# detectino-raspi.net
KiCad netlist of a schematic drawn in EAGLE
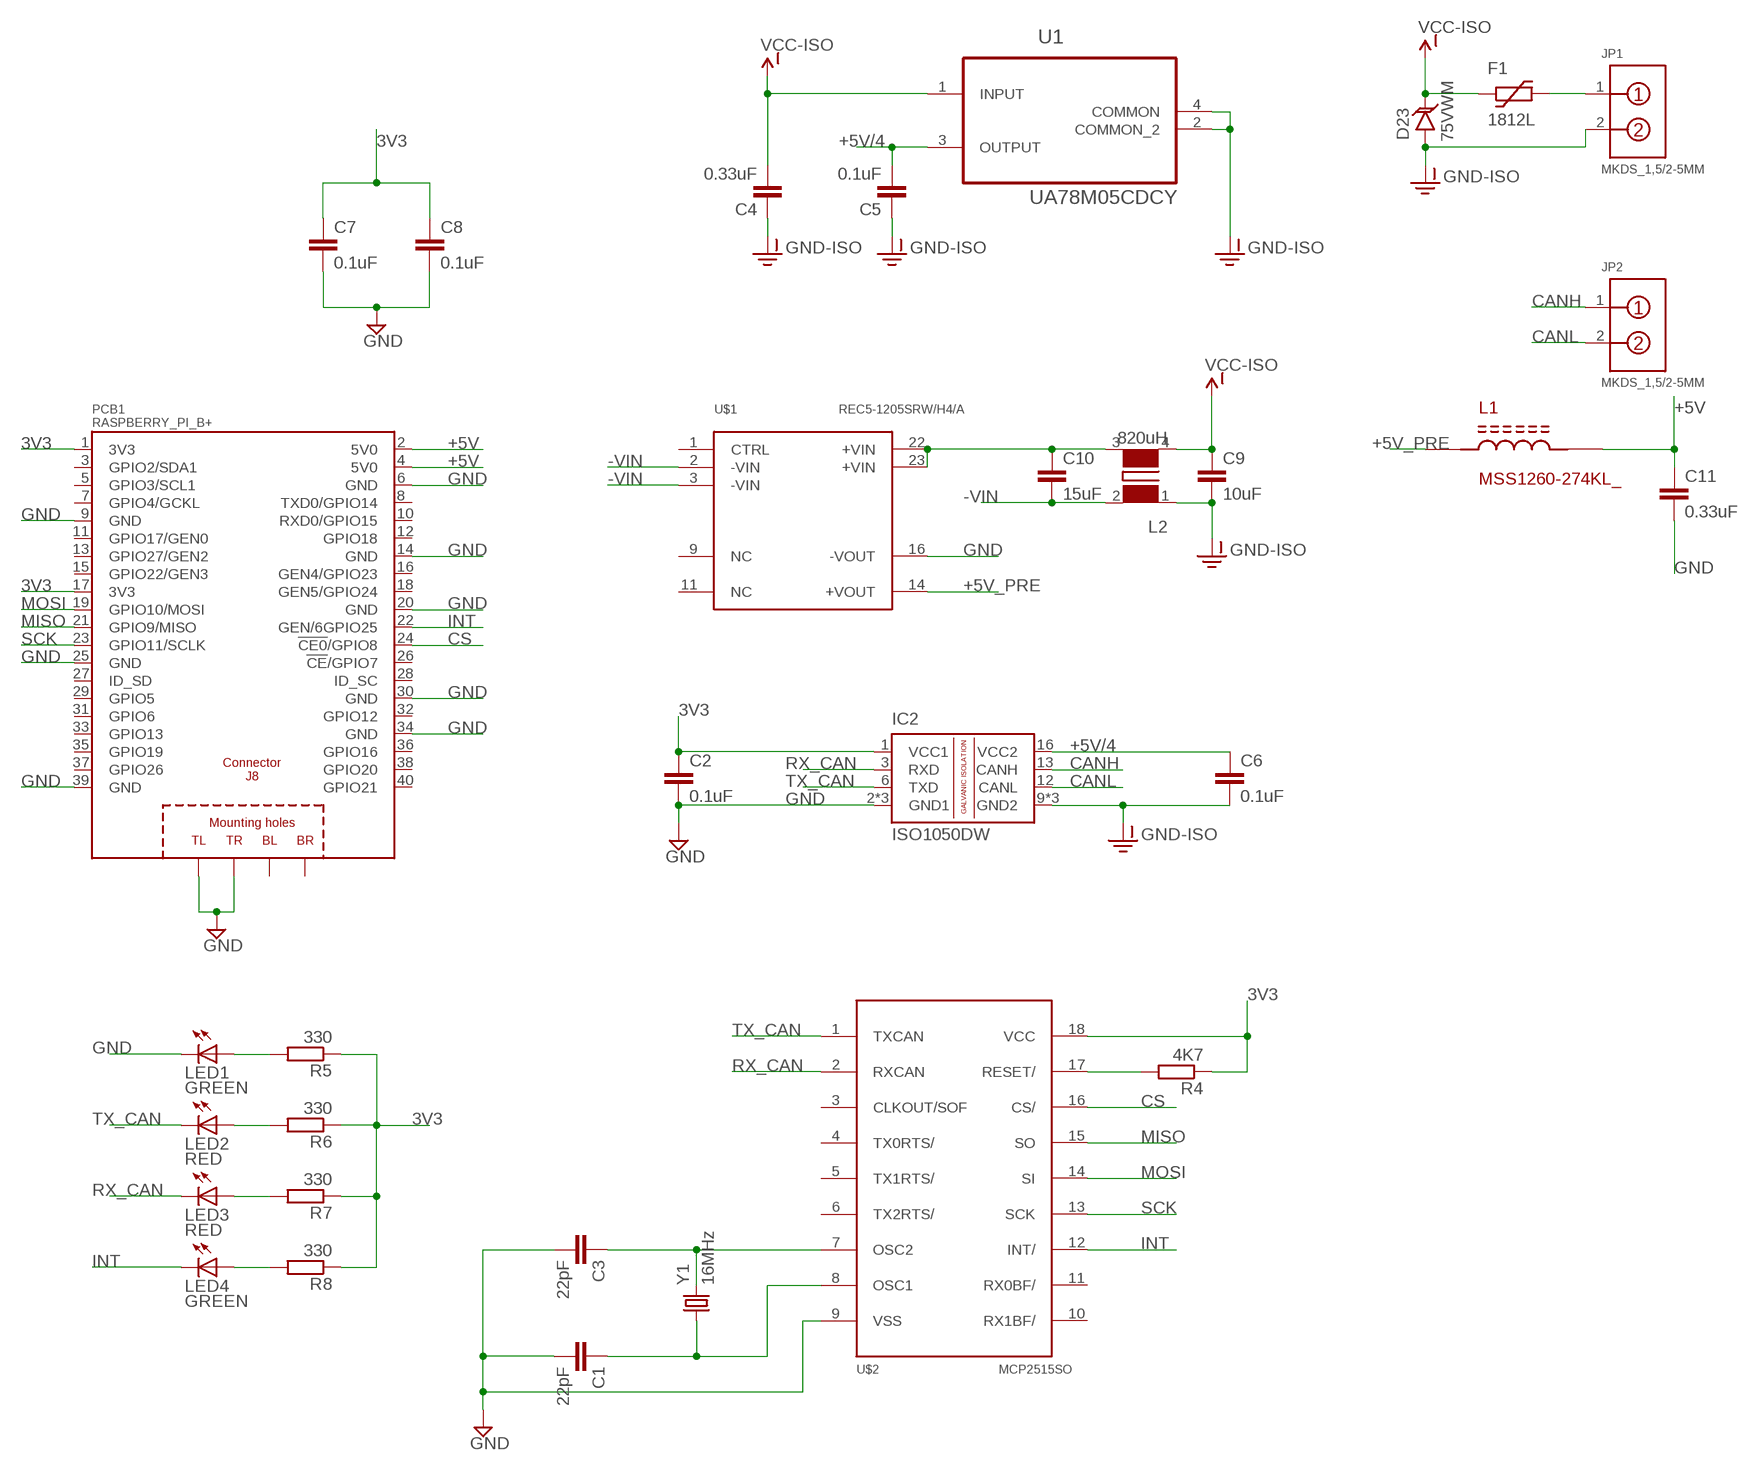
[diagram p0: schematic, sheet 1]

(export (version "E")
  (design (tool "Eeschema 10.0.6"))
  (components
    (comp (ref "C1")
      (value "22pF")
      (footprint "eagle-import:C1206K")
      (libsource (lib "eagle-import") (part "C-EUC1206K"))
    )
    (comp (ref "C2")
      (value "0.1uF")
      (footprint "eagle-import:C1206K")
      (libsource (lib "eagle-import") (part "C-EUC1206K"))
    )
    (comp (ref "C3")
      (value "22pF")
      (footprint "eagle-import:C1206K")
      (libsource (lib "eagle-import") (part "C-EUC1206K"))
    )
    (comp (ref "C4")
      (value "0.33uF")
      (footprint "eagle-import:C1206K")
      (libsource (lib "eagle-import") (part "C-EUC1206K"))
    )
    (comp (ref "C5")
      (value "0.1uF")
      (footprint "eagle-import:C1206K")
      (libsource (lib "eagle-import") (part "C-EUC1206K"))
    )
    (comp (ref "C6")
      (value "0.1uF")
      (footprint "eagle-import:C1206K")
      (libsource (lib "eagle-import") (part "C-EUC1206K"))
    )
    (comp (ref "C7")
      (value "0.1uF")
      (footprint "eagle-import:C1206K")
      (libsource (lib "eagle-import") (part "C-EUC1206K"))
    )
    (comp (ref "C8")
      (value "0.1uF")
      (footprint "eagle-import:C1206K")
      (libsource (lib "eagle-import") (part "C-EUC1206K"))
    )
    (comp (ref "C9")
      (value "10uF")
      (footprint "eagle-import:C1812K")
      (libsource (lib "eagle-import") (part "C-EUC1812K"))
    )
    (comp (ref "C10")
      (value "15uF")
      (footprint "eagle-import:C1812K")
      (libsource (lib "eagle-import") (part "C-EUC1812K"))
    )
    (comp (ref "C11")
      (value "0.33uF")
      (footprint "eagle-import:C1206K")
      (libsource (lib "eagle-import") (part "C-EUC1206K"))
    )
    (comp (ref "D23")
      (value "75VWM")
      (footprint "eagle-import:SMC")
      (libsource (lib "eagle-import") (part "TVS75VWM"))
    )
    (comp (ref "F1")
      (value "1812L")
      (footprint "eagle-import:1812L")
      (libsource (lib "eagle-import") (part "1812L"))
    )
    (comp (ref "IC2")
      (value "ISO1050DW")
      (footprint "eagle-import:SO-16DW")
      (libsource (lib "eagle-import") (part "ISO1050DW"))
    )
    (comp (ref "JP1")
      (value "MKDS_1,5/2-5MM")
      (footprint "eagle-import:MKDS_1,5_2-5MM")
      (libsource (lib "eagle-import") (part "MKDS_1,5/2-5MM"))
    )
    (comp (ref "JP2")
      (value "MKDS_1,5/2-5MM")
      (footprint "eagle-import:MKDS_1,5_2-5MM")
      (libsource (lib "eagle-import") (part "MKDS_1,5/2-5MM"))
    )
    (comp (ref "L1")
      (value "MSS1260-274KL_")
      (footprint "eagle-import:MSS1260")
      (libsource (lib "eagle-import") (part "MSS1260-274KL_"))
    )
    (comp (ref "L2")
      (value "820uH")
      (footprint "eagle-import:WE-FC_ET")
      (fields (field (name "MPN") "7448640395"))
      (libsource (lib "eagle-import") (part "WE-FC_ET-7448640395"))
    )
    (comp (ref "LED1")
      (value "GREEN")
      (footprint "eagle-import:SML1206")
      (libsource (lib "eagle-import") (part "LEDSML1206"))
    )
    (comp (ref "LED2")
      (value "RED")
      (footprint "eagle-import:SML1206")
      (libsource (lib "eagle-import") (part "LEDSML1206"))
    )
    (comp (ref "LED3")
      (value "RED")
      (footprint "eagle-import:SML1206")
      (libsource (lib "eagle-import") (part "LEDSML1206"))
    )
    (comp (ref "LED4")
      (value "GREEN")
      (footprint "eagle-import:SML1206")
      (libsource (lib "eagle-import") (part "LEDSML1206"))
    )
    (comp (ref "PCB1")
      (value "RASPBERRY_PI_B+")
      (footprint "eagle-import:RASPBERRY_PI_B+")
      (libsource (lib "eagle-import") (part "RASPBERRY_PI_B+"))
    )
    (comp (ref "R4")
      (value "4K7")
      (footprint "eagle-import:R1206")
      (libsource (lib "eagle-import") (part "R-EU_R1206"))
    )
    (comp (ref "R5")
      (value "330")
      (footprint "eagle-import:R1206")
      (libsource (lib "eagle-import") (part "R-EU_R1206"))
    )
    (comp (ref "R6")
      (value "330")
      (footprint "eagle-import:R1206")
      (libsource (lib "eagle-import") (part "R-EU_R1206"))
    )
    (comp (ref "R7")
      (value "330")
      (footprint "eagle-import:R1206")
      (libsource (lib "eagle-import") (part "R-EU_R1206"))
    )
    (comp (ref "R8")
      (value "330")
      (footprint "eagle-import:R1206")
      (libsource (lib "eagle-import") (part "R-EU_R1206"))
    )
    (comp (ref "U$1")
      (value "REC5-1205SRW/H4/A")
      (footprint "eagle-import:DIP24")
      (libsource (lib "eagle-import") (part "REC5-1205SRW/H4/A"))
    )
    (comp (ref "U$2")
      (value "MCP2515SO")
      (footprint "eagle-import:SO18L")
      (libsource (lib "eagle-import") (part "MCP2515SO"))
    )
    (comp (ref "U1")
      (value "UA78M05CDCY")
      (footprint "eagle-import:SOT230P700X180-4N")
      (libsource (lib "eagle-import") (part "UA78M05CDCY"))
    )
    (comp (ref "Y1")
      (value "16MHz")
      (footprint "eagle-import:HC49US")
      (libsource (lib "eagle-import") (part "CRYSTALHC49US"))
    )
  )
  (nets
    (net (code "1") (name "/+5V") (class "Default")
      (node (ref "C11") (pin "1") (pinfunction "1_1") (pintype "passive"))
      (node (ref "L1") (pin "P$2") (pinfunction "P$2_P$2") (pintype "bidirectional"))
      (node (ref "PCB1") (pin "2") (pinfunction "5V0_2") (pintype "power_in"))
      (node (ref "PCB1") (pin "4") (pinfunction "5V0_4") (pintype "power_in"))
    )
    (net (code "2") (name "/+5V_PRE") (class "Default")
      (node (ref "L1") (pin "P$1") (pinfunction "P$1_P$1") (pintype "bidirectional"))
      (node (ref "U$1") (pin "14") (pinfunction "+VOUT_14") (pintype "power_in"))
    )
    (net (code "3") (name "/+5V{slash}4") (class "Default")
      (node (ref "C5") (pin "2") (pinfunction "2_2") (pintype "passive"))
      (node (ref "C6") (pin "1") (pinfunction "1_1") (pintype "passive"))
      (node (ref "IC2") (pin "16") (pinfunction "VCC2_16") (pintype "input"))
      (node (ref "U1") (pin "3") (pinfunction "OUTPUT_3") (pintype "input"))
    )
    (net (code "4") (name "/-VIN") (class "Default")
      (node (ref "C10") (pin "2") (pinfunction "2_2") (pintype "passive"))
      (node (ref "L2") (pin "2") (pinfunction "4_2") (pintype "passive"))
      (node (ref "U$1") (pin "2") (pinfunction "-VIN_2") (pintype "power_in"))
      (node (ref "U$1") (pin "3") (pinfunction "-VIN_3") (pintype "power_in"))
    )
    (net (code "5") (name "/3V3") (class "Default")
      (node (ref "C2") (pin "1") (pinfunction "1_1") (pintype "passive"))
      (node (ref "C7") (pin "1") (pinfunction "1_1") (pintype "passive"))
      (node (ref "C8") (pin "1") (pinfunction "1_1") (pintype "passive"))
      (node (ref "IC2") (pin "1") (pinfunction "VCC1_1") (pintype "input"))
      (node (ref "PCB1") (pin "1") (pinfunction "3V3_1") (pintype "power_in"))
      (node (ref "PCB1") (pin "17") (pinfunction "3V3_17") (pintype "power_in"))
      (node (ref "R4") (pin "1") (pinfunction "1_1") (pintype "passive"))
      (node (ref "R5") (pin "1") (pinfunction "1_1") (pintype "passive"))
      (node (ref "R6") (pin "1") (pinfunction "1_1") (pintype "passive"))
      (node (ref "R7") (pin "1") (pinfunction "1_1") (pintype "passive"))
      (node (ref "R8") (pin "1") (pinfunction "1_1") (pintype "passive"))
      (node (ref "U$2") (pin "18") (pinfunction "VCC_18") (pintype "power_in"))
    )
    (net (code "6") (name "/CANH") (class "Default")
      (node (ref "IC2") (pin "13") (pinfunction "CANH_13") (pintype "input"))
      (node (ref "JP2") (pin "1") (pinfunction "P$1_1") (pintype "bidirectional"))
    )
    (net (code "7") (name "/CANL") (class "Default")
      (node (ref "IC2") (pin "12") (pinfunction "CANL_12") (pintype "input"))
      (node (ref "JP2") (pin "2") (pinfunction "P$2_2") (pintype "bidirectional"))
    )
    (net (code "8") (name "/CS") (class "Default")
      (node (ref "PCB1") (pin "24") (pinfunction "~{CE0}/GPIO8_24") (pintype "bidirectional"))
      (node (ref "U$2") (pin "16") (pinfunction "CS/_16") (pintype "input"))
    )
    (net (code "9") (name "/INT") (class "Default")
      (node (ref "LED4") (pin "C") (pinfunction "C_C") (pintype "passive"))
      (node (ref "PCB1") (pin "22") (pinfunction "GEN/6GPIO25_22") (pintype "bidirectional"))
      (node (ref "U$2") (pin "12") (pinfunction "INT/_12") (pintype "output"))
    )
    (net (code "10") (name "/MISO") (class "Default")
      (node (ref "PCB1") (pin "21") (pinfunction "GPIO9/MISO_21") (pintype "bidirectional"))
      (node (ref "U$2") (pin "15") (pinfunction "SO_15") (pintype "output"))
    )
    (net (code "11") (name "/MOSI") (class "Default")
      (node (ref "PCB1") (pin "19") (pinfunction "GPIO10/MOSI_19") (pintype "bidirectional"))
      (node (ref "U$2") (pin "14") (pinfunction "SI_14") (pintype "input"))
    )
    (net (code "12") (name "/RX_CAN") (class "Default")
      (node (ref "IC2") (pin "3") (pinfunction "RXD_3") (pintype "input"))
      (node (ref "LED3") (pin "C") (pinfunction "C_C") (pintype "passive"))
      (node (ref "U$2") (pin "2") (pinfunction "RXCAN_2") (pintype "input"))
    )
    (net (code "13") (name "/SCK") (class "Default")
      (node (ref "PCB1") (pin "23") (pinfunction "GPIO11/SCLK_23") (pintype "bidirectional"))
      (node (ref "U$2") (pin "13") (pinfunction "SCK_13") (pintype "input"))
    )
    (net (code "14") (name "/TX_CAN") (class "Default")
      (node (ref "IC2") (pin "6") (pinfunction "TXD_6") (pintype "input"))
      (node (ref "LED2") (pin "C") (pinfunction "C_C") (pintype "passive"))
      (node (ref "U$2") (pin "1") (pinfunction "TXCAN_1") (pintype "output"))
    )
    (net (code "15") (name "GND") (class "Default")
      (node (ref "C1") (pin "2") (pinfunction "2_2") (pintype "passive"))
      (node (ref "C11") (pin "2") (pinfunction "2_2") (pintype "passive"))
      (node (ref "C2") (pin "2") (pinfunction "2_2") (pintype "passive"))
      (node (ref "C3") (pin "2") (pinfunction "2_2") (pintype "passive"))
      (node (ref "C7") (pin "2") (pinfunction "2_2") (pintype "passive"))
      (node (ref "C8") (pin "2") (pinfunction "2_2") (pintype "passive"))
      (node (ref "IC2") (pin "2") (pinfunction "GND1_2") (pintype "input"))
      (node (ref "IC2") (pin "7") (pinfunction "GND1_7") (pintype "input"))
      (node (ref "IC2") (pin "8") (pinfunction "GND1_8") (pintype "input"))
      (node (ref "LED1") (pin "C") (pinfunction "C_C") (pintype "passive"))
      (node (ref "PCB1") (pin "14") (pinfunction "GND_14") (pintype "power_in"))
      (node (ref "PCB1") (pin "20") (pinfunction "GND_20") (pintype "power_in"))
      (node (ref "PCB1") (pin "25") (pinfunction "GND_25") (pintype "power_in"))
      (node (ref "PCB1") (pin "30") (pinfunction "GND_30") (pintype "power_in"))
      (node (ref "PCB1") (pin "34") (pinfunction "GND_34") (pintype "power_in"))
      (node (ref "PCB1") (pin "39") (pinfunction "GND_39") (pintype "power_in"))
      (node (ref "PCB1") (pin "6") (pinfunction "GND_6") (pintype "power_in"))
      (node (ref "PCB1") (pin "9") (pinfunction "GND_9") (pintype "power_in"))
      (node (ref "PCB1") (pin "PE_TL") (pinfunction "TL_PE_TL") (pintype "bidirectional"))
      (node (ref "PCB1") (pin "PE_TR") (pinfunction "TR_PE_TR") (pintype "bidirectional"))
      (node (ref "U$1") (pin "16") (pinfunction "-VOUT_16") (pintype "power_in"))
      (node (ref "U$2") (pin "9") (pinfunction "VSS_9") (pintype "power_in"))
    )
    (net (code "16") (name "GND-ISO") (class "Default")
      (node (ref "C4") (pin "1") (pinfunction "1_1") (pintype "passive"))
      (node (ref "C5") (pin "1") (pinfunction "1_1") (pintype "passive"))
      (node (ref "C6") (pin "2") (pinfunction "2_2") (pintype "passive"))
      (node (ref "C9") (pin "2") (pinfunction "2_2") (pintype "passive"))
      (node (ref "D23") (pin "A") (pinfunction "A_A") (pintype "passive"))
      (node (ref "IC2") (pin "10") (pinfunction "GND2_10") (pintype "input"))
      (node (ref "IC2") (pin "15") (pinfunction "GND2_15") (pintype "input"))
      (node (ref "IC2") (pin "9") (pinfunction "GND2_9") (pintype "input"))
      (node (ref "JP1") (pin "2") (pinfunction "P$2_2") (pintype "bidirectional"))
      (node (ref "L2") (pin "1") (pinfunction "1_1") (pintype "passive"))
      (node (ref "U1") (pin "2") (pinfunction "COMMON_2_2") (pintype "output"))
      (node (ref "U1") (pin "4") (pinfunction "COMMON_4") (pintype "output"))
    )
    (net (code "17") (name "Net-(C10-Pad1)") (class "Default")
      (node (ref "C10") (pin "1") (pinfunction "1_1") (pintype "passive"))
      (node (ref "L2") (pin "3") (pinfunction "3_3") (pintype "passive"))
      (node (ref "U$1") (pin "22") (pinfunction "+VIN_22") (pintype "power_in"))
      (node (ref "U$1") (pin "23") (pinfunction "+VIN_23") (pintype "power_in"))
    )
    (net (code "18") (name "Net-(F1-2)") (class "Default")
      (node (ref "F1") (pin "P$2") (pinfunction "2_P$2") (pintype "passive"))
      (node (ref "JP1") (pin "1") (pinfunction "P$1_1") (pintype "bidirectional"))
    )
    (net (code "19") (name "Net-(LED1-PadA)") (class "Default")
      (node (ref "LED1") (pin "A") (pinfunction "A_A") (pintype "passive"))
      (node (ref "R5") (pin "2") (pinfunction "2_2") (pintype "passive"))
    )
    (net (code "20") (name "Net-(LED2-PadA)") (class "Default")
      (node (ref "LED2") (pin "A") (pinfunction "A_A") (pintype "passive"))
      (node (ref "R6") (pin "2") (pinfunction "2_2") (pintype "passive"))
    )
    (net (code "21") (name "Net-(LED3-PadA)") (class "Default")
      (node (ref "LED3") (pin "A") (pinfunction "A_A") (pintype "passive"))
      (node (ref "R7") (pin "2") (pinfunction "2_2") (pintype "passive"))
    )
    (net (code "22") (name "Net-(LED4-PadA)") (class "Default")
      (node (ref "LED4") (pin "A") (pinfunction "A_A") (pintype "passive"))
      (node (ref "R8") (pin "2") (pinfunction "2_2") (pintype "passive"))
    )
    (net (code "23") (name "Net-(U$2-OSC1)") (class "Default")
      (node (ref "C1") (pin "1") (pinfunction "1_1") (pintype "passive"))
      (node (ref "U$2") (pin "8") (pinfunction "OSC1_8") (pintype "bidirectional"))
      (node (ref "Y1") (pin "1") (pinfunction "1_1") (pintype "passive"))
    )
    (net (code "24") (name "Net-(U$2-OSC2)") (class "Default")
      (node (ref "C3") (pin "1") (pinfunction "1_1") (pintype "passive"))
      (node (ref "U$2") (pin "7") (pinfunction "OSC2_7") (pintype "bidirectional"))
      (node (ref "Y1") (pin "2") (pinfunction "2_2") (pintype "passive"))
    )
    (net (code "25") (name "Net-(U$2-RESET{slash})") (class "Default")
      (node (ref "R4") (pin "2") (pinfunction "2_2") (pintype "passive"))
      (node (ref "U$2") (pin "17") (pinfunction "RESET/_17") (pintype "input"))
    )
    (net (code "26") (name "VCC-ISO") (class "Default")
      (node (ref "C4") (pin "2") (pinfunction "2_2") (pintype "passive"))
      (node (ref "C9") (pin "1") (pinfunction "1_1") (pintype "passive"))
      (node (ref "D23") (pin "C") (pinfunction "C_C") (pintype "passive"))
      (node (ref "F1") (pin "P$1") (pinfunction "1_P$1") (pintype "passive"))
      (node (ref "L2") (pin "4") (pinfunction "2_4") (pintype "passive"))
      (node (ref "U1") (pin "1") (pinfunction "INPUT_1") (pintype "input"))
    )
    (net (code "27") (name "unconnected-(PCB1-BL-PadPE_BL)") (class "Default")
      (node (ref "PCB1") (pin "PE_BL") (pinfunction "BL_PE_BL") (pintype "bidirectional"))
    )
    (net (code "28") (name "unconnected-(PCB1-BR-PadPE_BR)") (class "Default")
      (node (ref "PCB1") (pin "PE_BR") (pinfunction "BR_PE_BR") (pintype "bidirectional"))
    )
    (net (code "29") (name "unconnected-(PCB1-GEN4{slash}GPIO23-Pad16)") (class "Default")
      (node (ref "PCB1") (pin "16") (pinfunction "GEN4/GPIO23_16") (pintype "bidirectional"))
    )
    (net (code "30") (name "unconnected-(PCB1-GEN5{slash}GPIO24-Pad18)") (class "Default")
      (node (ref "PCB1") (pin "18") (pinfunction "GEN5/GPIO24_18") (pintype "bidirectional"))
    )
    (net (code "31") (name "unconnected-(PCB1-GPIO2{slash}SDA1-Pad3)") (class "Default")
      (node (ref "PCB1") (pin "3") (pinfunction "GPIO2/SDA1_3") (pintype "bidirectional"))
    )
    (net (code "32") (name "unconnected-(PCB1-GPIO3{slash}SCL1-Pad5)") (class "Default")
      (node (ref "PCB1") (pin "5") (pinfunction "GPIO3/SCL1_5") (pintype "bidirectional"))
    )
    (net (code "33") (name "unconnected-(PCB1-GPIO4{slash}GCKL-Pad7)") (class "Default")
      (node (ref "PCB1") (pin "7") (pinfunction "GPIO4/GCKL_7") (pintype "bidirectional"))
    )
    (net (code "34") (name "unconnected-(PCB1-GPIO5-Pad29)") (class "Default")
      (node (ref "PCB1") (pin "29") (pinfunction "GPIO5_29") (pintype "bidirectional"))
    )
    (net (code "35") (name "unconnected-(PCB1-GPIO6-Pad31)") (class "Default")
      (node (ref "PCB1") (pin "31") (pinfunction "GPIO6_31") (pintype "bidirectional"))
    )
    (net (code "36") (name "unconnected-(PCB1-GPIO12-Pad32)") (class "Default")
      (node (ref "PCB1") (pin "32") (pinfunction "GPIO12_32") (pintype "bidirectional"))
    )
    (net (code "37") (name "unconnected-(PCB1-GPIO13-Pad33)") (class "Default")
      (node (ref "PCB1") (pin "33") (pinfunction "GPIO13_33") (pintype "bidirectional"))
    )
    (net (code "38") (name "unconnected-(PCB1-GPIO16-Pad36)") (class "Default")
      (node (ref "PCB1") (pin "36") (pinfunction "GPIO16_36") (pintype "bidirectional"))
    )
    (net (code "39") (name "unconnected-(PCB1-GPIO17{slash}GEN0-Pad11)") (class "Default")
      (node (ref "PCB1") (pin "11") (pinfunction "GPIO17/GEN0_11") (pintype "bidirectional"))
    )
    (net (code "40") (name "unconnected-(PCB1-GPIO18-Pad12)") (class "Default")
      (node (ref "PCB1") (pin "12") (pinfunction "GPIO18_12") (pintype "bidirectional"))
    )
    (net (code "41") (name "unconnected-(PCB1-GPIO19-Pad35)") (class "Default")
      (node (ref "PCB1") (pin "35") (pinfunction "GPIO19_35") (pintype "bidirectional"))
    )
    (net (code "42") (name "unconnected-(PCB1-GPIO20-Pad38)") (class "Default")
      (node (ref "PCB1") (pin "38") (pinfunction "GPIO20_38") (pintype "bidirectional"))
    )
    (net (code "43") (name "unconnected-(PCB1-GPIO21-Pad40)") (class "Default")
      (node (ref "PCB1") (pin "40") (pinfunction "GPIO21_40") (pintype "bidirectional"))
    )
    (net (code "44") (name "unconnected-(PCB1-GPIO22{slash}GEN3-Pad15)") (class "Default")
      (node (ref "PCB1") (pin "15") (pinfunction "GPIO22/GEN3_15") (pintype "bidirectional"))
    )
    (net (code "45") (name "unconnected-(PCB1-GPIO26-Pad37)") (class "Default")
      (node (ref "PCB1") (pin "37") (pinfunction "GPIO26_37") (pintype "bidirectional"))
    )
    (net (code "46") (name "unconnected-(PCB1-GPIO27{slash}GEN2-Pad13)") (class "Default")
      (node (ref "PCB1") (pin "13") (pinfunction "GPIO27/GEN2_13") (pintype "bidirectional"))
    )
    (net (code "47") (name "unconnected-(PCB1-ID_SC-Pad28)") (class "Default")
      (node (ref "PCB1") (pin "28") (pinfunction "ID_SC_28") (pintype "bidirectional"))
    )
    (net (code "48") (name "unconnected-(PCB1-ID_SD-Pad27)") (class "Default")
      (node (ref "PCB1") (pin "27") (pinfunction "ID_SD_27") (pintype "bidirectional"))
    )
    (net (code "49") (name "unconnected-(PCB1-RXD0{slash}GPIO15-Pad10)") (class "Default")
      (node (ref "PCB1") (pin "10") (pinfunction "RXD0/GPIO15_10") (pintype "bidirectional"))
    )
    (net (code "50") (name "unconnected-(PCB1-TXD0{slash}GPIO14-Pad8)") (class "Default")
      (node (ref "PCB1") (pin "8") (pinfunction "TXD0/GPIO14_8") (pintype "bidirectional"))
    )
    (net (code "51") (name "unconnected-(PCB1-~{CE}{slash}GPIO7-Pad26)") (class "Default")
      (node (ref "PCB1") (pin "26") (pinfunction "~{CE}/GPIO7_26") (pintype "bidirectional"))
    )
    (net (code "52") (name "unconnected-(U$1-CTRL-Pad1)") (class "Default")
      (node (ref "U$1") (pin "1") (pinfunction "CTRL_1") (pintype "bidirectional"))
    )
    (net (code "53") (name "unconnected-(U$1-NC-Pad9)") (class "Default")
      (node (ref "U$1") (pin "9") (pinfunction "NC_9") (pintype "no_connect"))
    )
    (net (code "54") (name "unconnected-(U$1-NC-Pad11)") (class "Default")
      (node (ref "U$1") (pin "11") (pinfunction "NC_11") (pintype "no_connect"))
    )
    (net (code "55") (name "unconnected-(U$2-CLKOUT{slash}SOF-Pad3)") (class "Default")
      (node (ref "U$2") (pin "3") (pinfunction "CLKOUT/SOF_3") (pintype "bidirectional"))
    )
    (net (code "56") (name "unconnected-(U$2-RX0BF{slash}-Pad11)") (class "Default")
      (node (ref "U$2") (pin "11") (pinfunction "RX0BF/_11") (pintype "bidirectional"))
    )
    (net (code "57") (name "unconnected-(U$2-RX1BF{slash}-Pad10)") (class "Default")
      (node (ref "U$2") (pin "10") (pinfunction "RX1BF/_10") (pintype "bidirectional"))
    )
    (net (code "58") (name "unconnected-(U$2-TX0RTS{slash}-Pad4)") (class "Default")
      (node (ref "U$2") (pin "4") (pinfunction "TX0RTS/_4") (pintype "bidirectional"))
    )
    (net (code "59") (name "unconnected-(U$2-TX1RTS{slash}-Pad5)") (class "Default")
      (node (ref "U$2") (pin "5") (pinfunction "TX1RTS/_5") (pintype "bidirectional"))
    )
    (net (code "60") (name "unconnected-(U$2-TX2RTS{slash}-Pad6)") (class "Default")
      (node (ref "U$2") (pin "6") (pinfunction "TX2RTS/_6") (pintype "bidirectional"))
    )
  )
)
